# headphone_vu_schematic.net
KiCad netlist of a schematic drawn in EAGLE
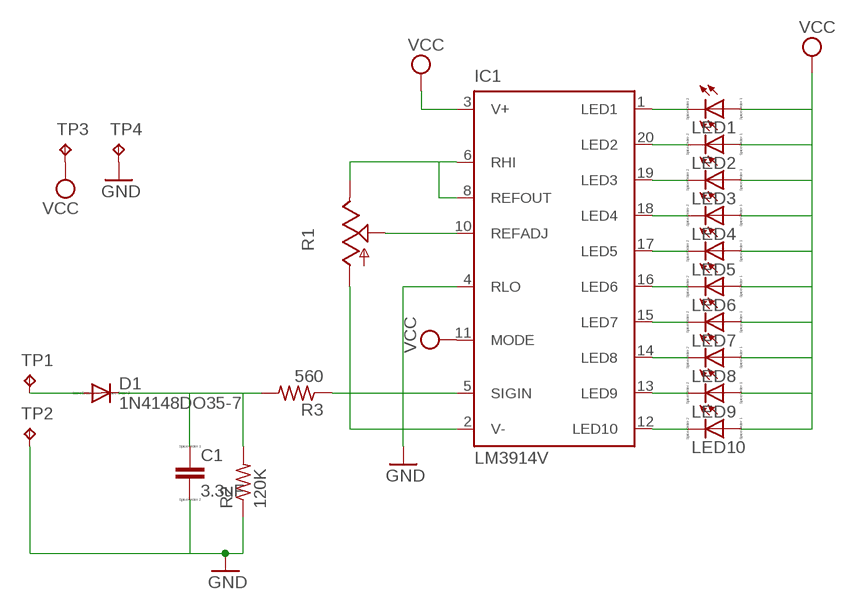
[diagram p0: schematic, sheet 1]

(export (version "E")
  (design (tool "Eeschema 10.0.6"))
  (components
    (comp (ref "C1")
      (value "3.3uF")
      (footprint "eagle-import:C0603")
      (libsource (lib "eagle-import") (part "CC0603"))
    )
    (comp (ref "D1")
      (value "1N4148DO35-7")
      (footprint "eagle-import:DO35-7")
      (libsource (lib "eagle-import") (part "1N4148DO35-7"))
    )
    (comp (ref "IC1")
      (value "LM3914V")
      (footprint "eagle-import:PLCC20S")
      (libsource (lib "eagle-import") (part "LM391V4"))
    )
    (comp (ref "LED1")
      (value "LED_E")
      (footprint "eagle-import:LED_1206")
      (libsource (lib "eagle-import") (part "LED_E"))
    )
    (comp (ref "LED2")
      (value "LED_E")
      (footprint "eagle-import:LED_1206")
      (libsource (lib "eagle-import") (part "LED_E"))
    )
    (comp (ref "LED3")
      (value "LED_E")
      (footprint "eagle-import:LED_1206")
      (libsource (lib "eagle-import") (part "LED_E"))
    )
    (comp (ref "LED4")
      (value "LED_E")
      (footprint "eagle-import:LED_1206")
      (libsource (lib "eagle-import") (part "LED_E"))
    )
    (comp (ref "LED5")
      (value "LED_E")
      (footprint "eagle-import:LED_1206")
      (libsource (lib "eagle-import") (part "LED_E"))
    )
    (comp (ref "LED6")
      (value "LED_E")
      (footprint "eagle-import:LED_1206")
      (libsource (lib "eagle-import") (part "LED_E"))
    )
    (comp (ref "LED7")
      (value "LED_E")
      (footprint "eagle-import:LED_1206")
      (libsource (lib "eagle-import") (part "LED_E"))
    )
    (comp (ref "LED8")
      (value "LED_E")
      (footprint "eagle-import:LED_1206")
      (libsource (lib "eagle-import") (part "LED_E"))
    )
    (comp (ref "LED9")
      (value "LED_E")
      (footprint "eagle-import:LED_1206")
      (libsource (lib "eagle-import") (part "LED_E"))
    )
    (comp (ref "LED10")
      (value "LED_E")
      (footprint "eagle-import:LED_1206")
      (libsource (lib "eagle-import") (part "LED_E"))
    )
    (comp (ref "R1")
      (value "TRIM_US-3223W")
      (footprint "eagle-import:3223W")
      (libsource (lib "eagle-import") (part "TRIM_US-3223W"))
    )
    (comp (ref "R2")
      (value "120K")
      (footprint "eagle-import:R0603")
      (libsource (lib "eagle-import") (part "R-US_R0603"))
    )
    (comp (ref "R3")
      (value "560")
      (footprint "eagle-import:R0603")
      (libsource (lib "eagle-import") (part "R-US_R0603"))
    )
    (comp (ref "TP1")
      (value "TPPAD1-20")
      (footprint "eagle-import:P1-20")
      (libsource (lib "eagle-import") (part "TPPAD1-20"))
    )
    (comp (ref "TP2")
      (value "TPPAD1-20")
      (footprint "eagle-import:P1-20")
      (libsource (lib "eagle-import") (part "TPPAD1-20"))
    )
    (comp (ref "TP3")
      (value "TPPAD1-20")
      (footprint "eagle-import:P1-20")
      (libsource (lib "eagle-import") (part "TPPAD1-20"))
    )
    (comp (ref "TP4")
      (value "TPPAD1-20")
      (footprint "eagle-import:P1-20")
      (libsource (lib "eagle-import") (part "TPPAD1-20"))
    )
  )
  (nets
    (net (code "1") (name "GND") (class "Default")
      (node (ref "C1") (pin "2") (pinfunction "2_2") (pintype "passive"))
      (node (ref "IC1") (pin "2") (pinfunction "V-_2") (pintype "power_in"))
      (node (ref "IC1") (pin "4") (pinfunction "RLO_4") (pintype "input"))
      (node (ref "R1") (pin "1") (pinfunction "A_1") (pintype "passive"))
      (node (ref "R2") (pin "1") (pinfunction "1_1") (pintype "passive"))
      (node (ref "TP2") (pin "TP") (pinfunction "TP_TP") (pintype "input"))
      (node (ref "TP4") (pin "TP") (pinfunction "TP_TP") (pintype "input"))
    )
    (net (code "2") (name "Net-(C1-Pad1)") (class "Default")
      (node (ref "C1") (pin "1") (pinfunction "1_1") (pintype "passive"))
      (node (ref "D1") (pin "C") (pinfunction "C_C") (pintype "passive"))
      (node (ref "R2") (pin "2") (pinfunction "2_2") (pintype "passive"))
      (node (ref "R3") (pin "2") (pinfunction "2_2") (pintype "passive"))
    )
    (net (code "3") (name "Net-(D1-PadA)") (class "Default")
      (node (ref "D1") (pin "A") (pinfunction "A_A") (pintype "passive"))
      (node (ref "TP1") (pin "TP") (pinfunction "TP_TP") (pintype "input"))
    )
    (net (code "4") (name "Net-(IC1-LED1)") (class "Default")
      (node (ref "IC1") (pin "1") (pinfunction "LED1_1") (pintype "output"))
      (node (ref "LED1") (pin "C") (pinfunction "C_C") (pintype "passive"))
    )
    (net (code "5") (name "Net-(IC1-LED2)") (class "Default")
      (node (ref "IC1") (pin "20") (pinfunction "LED2_20") (pintype "output"))
      (node (ref "LED2") (pin "C") (pinfunction "C_C") (pintype "passive"))
    )
    (net (code "6") (name "Net-(IC1-LED3)") (class "Default")
      (node (ref "IC1") (pin "19") (pinfunction "LED3_19") (pintype "output"))
      (node (ref "LED3") (pin "C") (pinfunction "C_C") (pintype "passive"))
    )
    (net (code "7") (name "Net-(IC1-LED4)") (class "Default")
      (node (ref "IC1") (pin "18") (pinfunction "LED4_18") (pintype "output"))
      (node (ref "LED4") (pin "C") (pinfunction "C_C") (pintype "passive"))
    )
    (net (code "8") (name "Net-(IC1-LED5)") (class "Default")
      (node (ref "IC1") (pin "17") (pinfunction "LED5_17") (pintype "output"))
      (node (ref "LED5") (pin "C") (pinfunction "C_C") (pintype "passive"))
    )
    (net (code "9") (name "Net-(IC1-LED6)") (class "Default")
      (node (ref "IC1") (pin "16") (pinfunction "LED6_16") (pintype "output"))
      (node (ref "LED6") (pin "C") (pinfunction "C_C") (pintype "passive"))
    )
    (net (code "10") (name "Net-(IC1-LED7)") (class "Default")
      (node (ref "IC1") (pin "15") (pinfunction "LED7_15") (pintype "output"))
      (node (ref "LED7") (pin "C") (pinfunction "C_C") (pintype "passive"))
    )
    (net (code "11") (name "Net-(IC1-LED8)") (class "Default")
      (node (ref "IC1") (pin "14") (pinfunction "LED8_14") (pintype "output"))
      (node (ref "LED8") (pin "C") (pinfunction "C_C") (pintype "passive"))
    )
    (net (code "12") (name "Net-(IC1-LED9)") (class "Default")
      (node (ref "IC1") (pin "13") (pinfunction "LED9_13") (pintype "output"))
      (node (ref "LED9") (pin "C") (pinfunction "C_C") (pintype "passive"))
    )
    (net (code "13") (name "Net-(IC1-LED10)") (class "Default")
      (node (ref "IC1") (pin "12") (pinfunction "LED10_12") (pintype "output"))
      (node (ref "LED10") (pin "C") (pinfunction "C_C") (pintype "passive"))
    )
    (net (code "14") (name "Net-(IC1-REFADJ)") (class "Default")
      (node (ref "IC1") (pin "10") (pinfunction "REFADJ_10") (pintype "passive"))
      (node (ref "R1") (pin "2") (pinfunction "S_2") (pintype "passive"))
    )
    (net (code "15") (name "Net-(IC1-REFOUT)") (class "Default")
      (node (ref "IC1") (pin "6") (pinfunction "RHI_6") (pintype "input"))
      (node (ref "IC1") (pin "8") (pinfunction "REFOUT_8") (pintype "output"))
      (node (ref "R1") (pin "3") (pinfunction "E_3") (pintype "passive"))
    )
    (net (code "16") (name "Net-(IC1-SIGIN)") (class "Default")
      (node (ref "IC1") (pin "5") (pinfunction "SIGIN_5") (pintype "input"))
      (node (ref "R3") (pin "1") (pinfunction "1_1") (pintype "passive"))
    )
    (net (code "17") (name "VCC") (class "Default")
      (node (ref "IC1") (pin "11") (pinfunction "MODE_11") (pintype "input"))
      (node (ref "IC1") (pin "3") (pinfunction "V+_3") (pintype "power_in"))
      (node (ref "LED1") (pin "A") (pinfunction "A_A") (pintype "passive"))
      (node (ref "LED10") (pin "A") (pinfunction "A_A") (pintype "passive"))
      (node (ref "LED2") (pin "A") (pinfunction "A_A") (pintype "passive"))
      (node (ref "LED3") (pin "A") (pinfunction "A_A") (pintype "passive"))
      (node (ref "LED4") (pin "A") (pinfunction "A_A") (pintype "passive"))
      (node (ref "LED5") (pin "A") (pinfunction "A_A") (pintype "passive"))
      (node (ref "LED6") (pin "A") (pinfunction "A_A") (pintype "passive"))
      (node (ref "LED7") (pin "A") (pinfunction "A_A") (pintype "passive"))
      (node (ref "LED8") (pin "A") (pinfunction "A_A") (pintype "passive"))
      (node (ref "LED9") (pin "A") (pinfunction "A_A") (pintype "passive"))
      (node (ref "TP3") (pin "TP") (pinfunction "TP_TP") (pintype "input"))
    )
  )
)
